# Isolated-Power-Section.net
KiCad netlist of a schematic drawn in Altium Designer
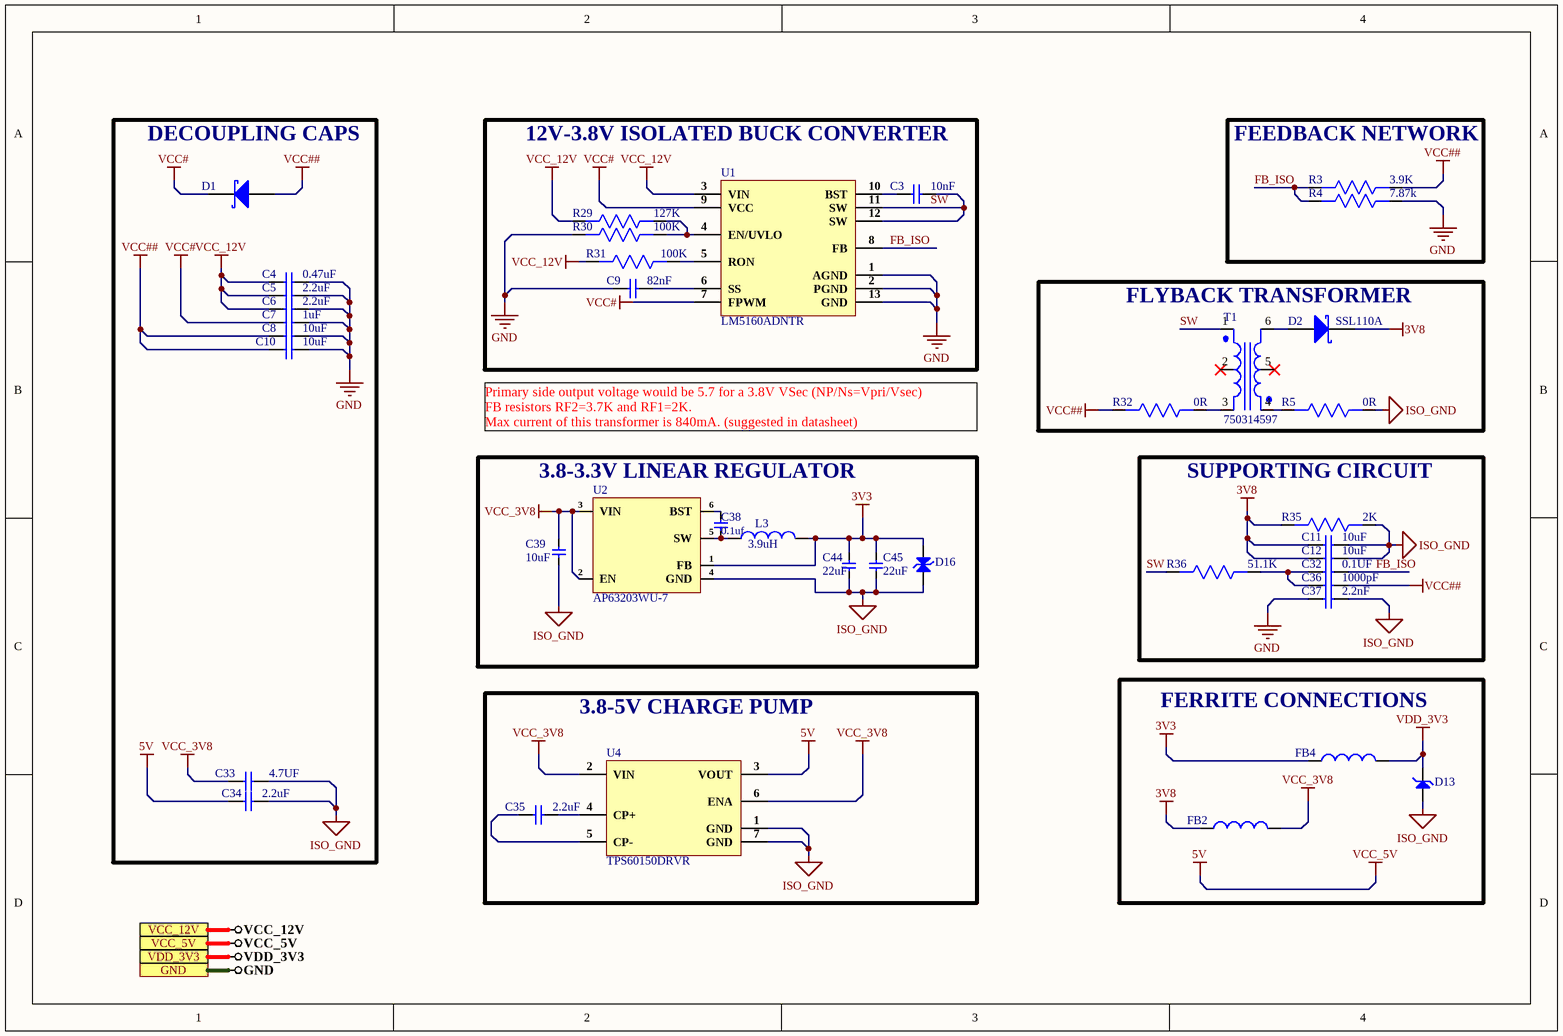
[diagram p0: Isolated-Power-Section.SchDoc]

(export (version "E")
  (design (tool "Eeschema 10.0.6"))
  (components
    (comp (ref "C3")
      (value "10nF")
      (footprint "Cap 0402")
      (description "CAP CER 10000PF 25V X7R 0402")
      (fields
        (field (name "MANUFACTURER") "Yageo")
        (field (name "MANUFACTURER PART NUMBER") "CC0402KRX7R8BB103")
      )
      (libsource (lib "Cole_Benson") (part "CC0402KRX7R8BB103"))
    )
    (comp (ref "C4")
      (value "0.47uF")
      (footprint "Cap 0402")
      (description "CAP CER 0.47UF 50V X5R 0402")
      (fields
        (field (name "MANUFACTURER") "Taiyo Yuden")
        (field (name "MANUFACTURER PART NUMBER") "UMK105ABJ474KV-F")
      )
      (libsource (lib "Cole_Benson") (part "UMK105ABJ474KV-F"))
    )
    (comp (ref "C5")
      (value "2.2uF")
      (footprint "Cap 0603")
      (description "CAP, 2.2µF, 35V, 10%, X5R, 0603")
      (fields
        (field (name "MANUFACTURER") "Murata")
        (field (name "MANUFACTURER PART NUMBER") "GRM188R6YA225KA12D")
      )
      (libsource (lib "Cole_Benson") (part "GRM188R6YA225KA12D"))
    )
    (comp (ref "C6")
      (value "2.2uF")
      (footprint "Cap 0603")
      (description "CAP, 2.2µF, 35V, 10%, X5R, 0603")
      (fields
        (field (name "MANUFACTURER") "Murata")
        (field (name "MANUFACTURER PART NUMBER") "GRM188R6YA225KA12D")
      )
      (libsource (lib "Cole_Benson") (part "GRM188R6YA225KA12D"))
    )
    (comp (ref "C7")
      (value "1uF")
      (footprint "Cap 0603")
      (description "CAP CER 1UF 25V X5R 0603")
      (fields
        (field (name "MANUFACTURER") "Yageo")
        (field (name "MANUFACTURER PART NUMBER") "CC0603KRX5R8BB105")
      )
      (libsource (lib "Cole_Benson") (part "CC0603KRX5R8BB105"))
    )
    (comp (ref "C8")
      (value "10uF")
      (footprint "Cap 0603")
      (description "10uF 35V X5R 20% Pad SMD 0603")
      (fields
        (field (name "MANUFACTURER") "Murata")
        (field (name "MANUFACTURER PART NUMBER") "GRM188R6YA106MA73D")
      )
      (libsource (lib "Cole_Benson") (part "GRM188R6YA106MA73D"))
    )
    (comp (ref "C9")
      (value "82nF")
      (footprint "Cap 0603")
      (description "CAP CER 0.082UF 50V X7R 0603")
      (fields
        (field (name "MANUFACTURER") "Yageo")
        (field (name "MANUFACTURER PART NUMBER") "CC0603KRX7R9BB823")
      )
      (libsource (lib "Cole_Benson") (part "CC0603KRX7R9BB823"))
    )
    (comp (ref "C10")
      (value "10uF")
      (footprint "Cap 0603")
      (description "10uF 35V X5R 20% Pad SMD 0603")
      (fields
        (field (name "MANUFACTURER") "Murata")
        (field (name "MANUFACTURER PART NUMBER") "GRM188R6YA106MA73D")
      )
      (libsource (lib "Cole_Benson") (part "GRM188R6YA106MA73D"))
    )
    (comp (ref "C11")
      (value "10uF")
      (footprint "Cap 0603")
      (description "10uF 35V X5R 20% Pad SMD 0603")
      (fields
        (field (name "MANUFACTURER") "Murata")
        (field (name "MANUFACTURER PART NUMBER") "GRM188R6YA106MA73D")
      )
      (libsource (lib "Cole_Benson") (part "GRM188R6YA106MA73D"))
    )
    (comp (ref "C12")
      (value "10uF")
      (footprint "Cap 0603")
      (description "10uF 35V X5R 20% Pad SMD 0603")
      (fields
        (field (name "MANUFACTURER") "Murata")
        (field (name "MANUFACTURER PART NUMBER") "GRM188R6YA106MA73D")
      )
      (libsource (lib "Cole_Benson") (part "GRM188R6YA106MA73D"))
    )
    (comp (ref "C32")
      (value "0.1UF")
      (footprint "Cap 0402")
      (description "CAP CER 0.1UF 50V X7R 0402")
      (fields
        (field (name "MANUFACTURER") "Samsung")
        (field (name "MANUFACTURER PART NUMBER") "CL05B104KB54PNC")
      )
      (libsource (lib "Cole_Benson") (part "CL05B104KB54PNC"))
    )
    (comp (ref "C33")
      (value "4.7UF")
      (footprint "Cap 0603")
      (description "CAP CER 4.7UF 25V X5R 0603")
      (fields
        (field (name "MANUFACTURER") "Samsung")
        (field (name "MANUFACTURER PART NUMBER") "CL10A475KA8NQNC")
      )
      (libsource (lib "Cole_Benson") (part "CL10A475KA8NQNC"))
    )
    (comp (ref "C34")
      (value "2.2uF")
      (footprint "Cap 0603")
      (description "CAP, 2.2µF, 35V, 10%, X5R, 0603")
      (fields
        (field (name "MANUFACTURER") "Murata")
        (field (name "MANUFACTURER PART NUMBER") "GRM188R6YA225KA12D")
      )
      (libsource (lib "Cole_Benson") (part "GRM188R6YA225KA12D"))
    )
    (comp (ref "C35")
      (value "2.2uF")
      (footprint "Cap 0603")
      (description "CAP, 2.2µF, 35V, 10%, X5R, 0603")
      (fields
        (field (name "MANUFACTURER") "Murata")
        (field (name "MANUFACTURER PART NUMBER") "GRM188R6YA225KA12D")
      )
      (libsource (lib "Cole_Benson") (part "GRM188R6YA225KA12D"))
    )
    (comp (ref "C36")
      (value "1000pF")
      (footprint "Cap 0402")
      (description "CAP CER 1000PF 100V X7R 0402")
      (fields
        (field (name "MANUFACTURER") "Wurth Electronics")
        (field (name "MANUFACTURER PART NUMBER") "885012205080")
      )
      (libsource (lib "Cole_Benson") (part "885012205080"))
    )
    (comp (ref "C37")
      (value "2.2nF")
      (footprint "Cap 0603")
      (description "CAP CER 2200PF 50V X7R 0603")
      (fields
        (field (name "MANUFACTURER") "Yageo")
        (field (name "MANUFACTURER PART NUMBER") "CC0603KRX7R9BB222")
      )
      (libsource (lib "Cole_Benson") (part "CC0603KRX7R9BB222"))
    )
    (comp (ref "C38")
      (value "0.1uf")
      (footprint "Cap-0402")
      (description "CAP CER 0.1UF 100V X5R 0402")
      (fields
        (field (name "MANUFACTURER") "Murata")
        (field (name "MANUFACTURER PART NUMBER") "GRM155R62A104KE14D")
      )
      (libsource (lib "eSpark Libraries") (part "GRM155R62A104KE14D"))
    )
    (comp (ref "C39")
      (value "10uF")
      (footprint "Cap-0603")
      (description "CAP CER 10UF 25V X5R 0603")
      (fields
        (field (name "MANUFACTURER") "TDK")
        (field (name "MANUFACTURER PART NUMBER") "C1608X5R1E106M080AC")
      )
      (libsource (lib "eSpark Libraries") (part "C1608X5R1E106M080AC"))
    )
    (comp (ref "C44")
      (value "22uF")
      (footprint "Cap-0805")
      (description "CAP CER 22UF 35V X5R 0805")
      (fields
        (field (name "MANUFACTURER") "TDK Corporation")
        (field (name "MANUFACTURER PART NUMBER") "C2012X5R1V226MT000E")
      )
      (libsource (lib "eSpark Libraries") (part "C2012X5R1V226MT000E"))
    )
    (comp (ref "C45")
      (value "22uF")
      (footprint "Cap-0805")
      (description "CAP CER 22UF 35V X5R 0805")
      (fields
        (field (name "MANUFACTURER") "TDK Corporation")
        (field (name "MANUFACTURER PART NUMBER") "C2012X5R1V226MT000E")
      )
      (libsource (lib "eSpark Libraries") (part "C2012X5R1V226MT000E"))
    )
    (comp (ref "D1")
      (value "CUS10S30,H3F")
      (footprint "CUS10S30,H3F")
      (description "Diode Schottky 30V 1A Surface Mount USC")
      (fields (field (name "MANUFACTURER") "Toshiba"))
      (libsource (lib "Cole_Benson") (part "CUS10S30,H3F"))
    )
    (comp (ref "D2")
      (value "SSL110A")
      (footprint "SMA")
      (description "500μA@100V 100V Single 600mV@1A 1A SMA Schottky Barrier Diodes (SBD) ROHS")
      (fields (field (name "MANUFACTURER") "Yangzhou"))
      (libsource (lib "Cole_Benson") (part "SSL110A"))
    )
    (comp (ref "D13")
      (value "1SMA5913BT3G-MS")
      (footprint "SMA")
      (description "Single 1.5W 3.13V~3.47V 3.3V SMA Zener Diodes ROHS")
      (fields (field (name "MANUFACTURER") "MSKSEMI") (field (name "LCSC PART NUMBER") "C18547722"))
      (libsource (lib "Cole_Benson") (part "1SMA5913BT3G-MS"))
    )
    (comp (ref "D16")
      (value "ESDM2033MX4T5G")
      (footprint "2-DFN (0.6x0.3)")
      (description "DIODE BIDIR ESD X4DFN2")
      (fields (field (name "MANUFACTURER") "ON Semiconductor") (field (name "LCSC PART NUMBER") "C896720"))
      (libsource (lib "Cole_Benson") (part "ESDM2033MX4T5G"))
    )
    (comp (ref "FB2")
      (value "MPZ1608S121ATDH5")
      (footprint "MPZ1608S121ATDH5")
      (description "Ferrite Beads Multi-Layer 120Ohm 25% 100MHz 2A 45mOhm DCR 0603 Automotive T/R")
      (fields (field (name "MANUFACTURER") "TDK") (field (name "TOLERANCE") "25%"))
      (libsource (lib "Cole_Benson") (part "MPZ1608S121ATDH5"))
    )
    (comp (ref "FB4")
      (value "MPZ1608S121ATDH5")
      (footprint "MPZ1608S121ATDH5")
      (description "Ferrite Beads Multi-Layer 120Ohm 25% 100MHz 2A 45mOhm DCR 0603 Automotive T/R")
      (fields (field (name "MANUFACTURER") "TDK") (field (name "TOLERANCE") "25%"))
      (libsource (lib "Cole_Benson") (part "MPZ1608S121ATDH5"))
    )
    (comp (ref "L3")
      (value "3.9uH")
      (footprint "FNR3015S3R9MT")
      (description "1.5A 3.9uH ±20% 1.4A SMD,3x3mm Power Inductors ROHS")
      (fields
        (field (name "MANUFACTURER") "cjiang")
        (field (name "MANUFACTURER PART NUMBER") "FNR3015S3R9MT")
      )
      (libsource (lib "Cole_Benson") (part "FNR3015S3R9MT"))
    )
    (comp (ref "R3")
      (value "3.9K")
      (footprint "Res0603")
      (description "Res 0603 3.9K Ohm 1% 0.1W(1/10W) ±100ppm/°C Pad SMD T/R")
      (fields
        (field (name "MANUFACTURER") "Yageo")
        (field (name "MANUFACTURER PART NUMBER") "RC0603FR-073K9L")
      )
      (libsource (lib "Cole_Benson") (part "RC0603FR-073K9L"))
    )
    (comp (ref "R4")
      (value "7.87k")
      (footprint "Res0603")
      (description "100mW 50V ±1% ±100ppm/℃ -55℃~+155℃ 7.87kΩ 0603 Chip Resistor - Surface Mount ROHS")
      (fields (field (name "MANUFACTURER") "FH") (field (name "MANUFACTURER PART NUMBER") "RS-03K7871FT"))
      (libsource (lib "Cole_Benson") (part "RS-03K7871FT"))
    )
    (comp (ref "R5")
      (value "0R")
      (footprint "Res0603")
      (description "RES SMD 0R, 1%, 0.1W, 0603")
      (fields
        (field (name "MANUFACTURER") "Yageo")
        (field (name "MANUFACTURER PART NUMBER") "RC0603FR-070RL")
      )
      (libsource (lib "Cole_Benson") (part "RC0603FR-070RL"))
    )
    (comp (ref "R29")
      (value "127K")
      (footprint "Res0603")
      (description "RES SMD 127K OHM 1% 1/10W 0603")
      (fields
        (field (name "MANUFACTURER") "Yageo")
        (field (name "MANUFACTURER PART NUMBER") "RT0603FRE07127KL")
      )
      (libsource (lib "Cole_Benson") (part "RT0603FRE07127KL"))
    )
    (comp (ref "R30")
      (value "100K")
      (footprint "Res0603")
      (description "Res Thick Film 0603 100K Ohm 5% 1/10W 100ppm/C Molded SMD SMD Paper T/R")
      (fields
        (field (name "MANUFACTURER") "Yageo")
        (field (name "MANUFACTURER PART NUMBER") "RC0603JR-07100KL")
      )
      (libsource (lib "Cole_Benson") (part "RC0603JR-07100KL"))
    )
    (comp (ref "R31")
      (value "100K")
      (footprint "Res0603")
      (description "Res Thick Film 0603 100K Ohm 5% 1/10W 100ppm/C Molded SMD SMD Paper T/R")
      (fields
        (field (name "MANUFACTURER") "Yageo")
        (field (name "MANUFACTURER PART NUMBER") "RC0603JR-07100KL")
      )
      (libsource (lib "Cole_Benson") (part "RC0603JR-07100KL"))
    )
    (comp (ref "R32")
      (value "0R")
      (footprint "Res0603")
      (description "RES SMD 0R, 1%, 0.1W, 0603")
      (fields
        (field (name "MANUFACTURER") "Yageo")
        (field (name "MANUFACTURER PART NUMBER") "RC0603FR-070RL")
      )
      (libsource (lib "Cole_Benson") (part "RC0603FR-070RL"))
    )
    (comp (ref "R35")
      (value "2K")
      (footprint "Res0603")
      (description "RES SMD 2K OHM 1% 1/10W 0603")
      (fields
        (field (name "MANUFACTURER") "Yageo")
        (field (name "MANUFACTURER PART NUMBER") "RC0603FR-072KL")
      )
      (libsource (lib "Cole_Benson") (part "RC0603FR-072KL"))
    )
    (comp (ref "R36")
      (value "51.1K")
      (footprint "Res0603")
      (description "Res SMD 0603 51.1K Ohm 0.1% 1/10W")
      (fields
        (field (name "MANUFACTURER") "Panasonic")
        (field (name "MANUFACTURER PART NUMBER") "ERA-3AEB5112V")
      )
      (libsource (lib "Cole_Benson") (part "ERA3AEB5112V"))
    )
    (comp (ref "T1")
      (value "750314597")
      (footprint "750314597")
      (description "XFRMR ISOL BUCK DC/DC CONV SMD")
      (fields (field (name "MANUFACTURER") "Wurth Electronics Midcom"))
      (libsource (lib "Cole_Benson") (part "750314597"))
    )
    (comp (ref "U1")
      (value "LM5160ADNTR")
      (footprint "LM5160ADNTR")
      (description "IC REG BUCK FLYBCK ADJ 12WSON")
      (fields (field (name "MANUFACTURER") "Texas Instruments"))
      (libsource (lib "Cole_Benson") (part "LM5160ADNTR"))
    )
    (comp (ref "U2")
      (value "AP63203WU-7")
      (footprint "TSOT-23-6")
      (description "IC REG BUCK 3.3V 2A TSOT26")
      (fields (field (name "MANUFACTURER") "Diodes") (field (name "LCSC PART NUMBER") "C780769"))
      (libsource (lib "eSpark Libraries") (part "AP63203WU-7"))
    )
    (comp (ref "U4")
      (value "TPS60150DRVR")
      (footprint "TPS60150DRVR")
      (description "IC REG CHARGE PUMP 5V 140MA 6SON")
      (fields (field (name "MANUFACTURER") "Texas Instruments"))
      (libsource (lib "Cole_Benson") (part "TPS60150DRVR"))
    )
  )
  (nets
    (net (code "1") (name "/FB_ISO") (class "Default")
      (node (ref "C32") (pin "2") (pinfunction "2_2") (pintype "passive"))
      (node (ref "R3") (pin "2") (pintype "passive"))
      (node (ref "R4") (pin "2") (pintype "passive"))
      (node (ref "U1") (pin "8") (pinfunction "FB_8") (pintype "passive"))
    )
    (net (code "2") (name "/SW") (class "Default")
      (node (ref "C3") (pin "2") (pinfunction "2_2") (pintype "passive"))
      (node (ref "R36") (pin "2") (pintype "passive"))
      (node (ref "T1") (pin "1") (pinfunction "PRI_1_1") (pintype "passive"))
      (node (ref "U1") (pin "11") (pinfunction "SW_11") (pintype "passive"))
      (node (ref "U1") (pin "12") (pinfunction "SW_12") (pintype "passive"))
    )
    (net (code "3") (name "3V3") (class "Default")
      (node (ref "C44") (pin "2") (pinfunction "2_2") (pintype "passive"))
      (node (ref "C45") (pin "2") (pinfunction "2_2") (pintype "passive"))
      (node (ref "D16") (pin "2") (pinfunction "A_2") (pintype "passive"))
      (node (ref "FB4") (pin "1") (pinfunction "1_1") (pintype "passive"))
      (node (ref "L3") (pin "2") (pinfunction "2_2") (pintype "passive"))
      (node (ref "U2") (pin "1") (pinfunction "FB_1") (pintype "passive"))
    )
    (net (code "4") (name "3V8") (class "Default")
      (node (ref "C11") (pin "1") (pinfunction "1_1") (pintype "passive"))
      (node (ref "C12") (pin "1") (pinfunction "1_1") (pintype "passive"))
      (node (ref "D2") (pin "1") (pinfunction "K_1") (pintype "passive"))
      (node (ref "FB2") (pin "1") (pinfunction "1_1") (pintype "passive"))
      (node (ref "R35") (pin "2") (pintype "passive"))
    )
    (net (code "5") (name "5V") (class "Default")
      (node (ref "C34") (pin "1") (pinfunction "1_1") (pintype "passive"))
      (node (ref "U4") (pin "3") (pinfunction "VOUT_3") (pintype "passive"))
    )
    (net (code "6") (name "GND") (class "Default")
      (node (ref "C10") (pin "2") (pinfunction "2_2") (pintype "passive"))
      (node (ref "C37") (pin "1") (pinfunction "1_1") (pintype "passive"))
      (node (ref "C4") (pin "2") (pinfunction "2_2") (pintype "passive"))
      (node (ref "C5") (pin "2") (pinfunction "2_2") (pintype "passive"))
      (node (ref "C6") (pin "2") (pinfunction "2_2") (pintype "passive"))
      (node (ref "C7") (pin "2") (pinfunction "2_2") (pintype "passive"))
      (node (ref "C8") (pin "2") (pinfunction "2_2") (pintype "passive"))
      (node (ref "C9") (pin "1") (pinfunction "1_1") (pintype "passive"))
      (node (ref "R30") (pin "2") (pintype "passive"))
      (node (ref "R4") (pin "1") (pintype "passive"))
      (node (ref "U1") (pin "1") (pinfunction "AGND_1") (pintype "passive"))
      (node (ref "U1") (pin "13") (pinfunction "GND_13") (pintype "passive"))
      (node (ref "U1") (pin "2") (pinfunction "PGND_2") (pintype "passive"))
    )
    (net (code "7") (name "ISO_GND") (class "Default")
      (node (ref "C11") (pin "2") (pinfunction "2_2") (pintype "passive"))
      (node (ref "C12") (pin "2") (pinfunction "2_2") (pintype "passive"))
      (node (ref "C33") (pin "2") (pinfunction "2_2") (pintype "passive"))
      (node (ref "C34") (pin "2") (pinfunction "2_2") (pintype "passive"))
      (node (ref "C37") (pin "2") (pinfunction "2_2") (pintype "passive"))
      (node (ref "C39") (pin "1") (pinfunction "1_1") (pintype "passive"))
      (node (ref "C44") (pin "1") (pinfunction "1_1") (pintype "passive"))
      (node (ref "C45") (pin "1") (pinfunction "1_1") (pintype "passive"))
      (node (ref "D13") (pin "2") (pinfunction "A_2") (pintype "passive"))
      (node (ref "D16") (pin "1") (pinfunction "A_1") (pintype "passive"))
      (node (ref "R35") (pin "1") (pintype "passive"))
      (node (ref "R5") (pin "1") (pintype "passive"))
      (node (ref "U2") (pin "4") (pinfunction "GND_4") (pintype "passive"))
      (node (ref "U4") (pin "1") (pinfunction "GND_1") (pintype "passive"))
      (node (ref "U4") (pin "7") (pinfunction "GND_7") (pintype "passive"))
    )
    (net (code "8") (name "Net-(C32-Pad1)") (class "Default")
      (node (ref "C32") (pin "1") (pinfunction "1_1") (pintype "passive"))
      (node (ref "C36") (pin "1") (pinfunction "1_1") (pintype "passive"))
      (node (ref "R36") (pin "1") (pintype "passive"))
    )
    (net (code "9") (name "Net-(D2-A)") (class "Default")
      (node (ref "D2") (pin "2") (pinfunction "A_2") (pintype "passive"))
      (node (ref "T1") (pin "6") (pinfunction "SEC_2_6") (pintype "passive"))
    )
    (net (code "10") (name "Net-(T1-PRI_2)") (class "Default")
      (node (ref "R32") (pin "1") (pintype "passive"))
      (node (ref "T1") (pin "3") (pinfunction "PRI_2_3") (pintype "passive"))
    )
    (net (code "11") (name "Net-(T1-SEC_1)") (class "Default")
      (node (ref "R5") (pin "2") (pintype "passive"))
      (node (ref "T1") (pin "4") (pinfunction "SEC_1_4") (pintype "passive"))
    )
    (net (code "12") (name "Net-(U1-BST)") (class "Default")
      (node (ref "C3") (pin "1") (pinfunction "1_1") (pintype "passive"))
      (node (ref "U1") (pin "10") (pinfunction "BST_10") (pintype "passive"))
    )
    (net (code "13") (name "Net-(U1-EN{slash}UVLO)") (class "Default")
      (node (ref "R29") (pin "1") (pintype "passive"))
      (node (ref "R30") (pin "1") (pintype "passive"))
      (node (ref "U1") (pin "4") (pinfunction "EN/UVLO_4") (pintype "passive"))
    )
    (net (code "14") (name "Net-(U1-RON)") (class "Default")
      (node (ref "R31") (pin "1") (pintype "passive"))
      (node (ref "U1") (pin "5") (pinfunction "RON_5") (pintype "passive"))
    )
    (net (code "15") (name "Net-(U1-SS)") (class "Default")
      (node (ref "C9") (pin "2") (pinfunction "2_2") (pintype "passive"))
      (node (ref "U1") (pin "6") (pinfunction "SS_6") (pintype "passive"))
    )
    (net (code "16") (name "Net-(U2-BST)") (class "Default")
      (node (ref "C38") (pin "2") (pinfunction "2_2") (pintype "passive"))
      (node (ref "U2") (pin "6") (pinfunction "BST_6") (pintype "passive"))
    )
    (net (code "17") (name "Net-(U2-SW)") (class "Default")
      (node (ref "C38") (pin "1") (pinfunction "1_1") (pintype "passive"))
      (node (ref "L3") (pin "1") (pinfunction "1_1") (pintype "passive"))
      (node (ref "U2") (pin "5") (pinfunction "SW_5") (pintype "passive"))
    )
    (net (code "18") (name "Net-(U4-CP+)") (class "Default")
      (node (ref "C35") (pin "2") (pinfunction "2_2") (pintype "passive"))
      (node (ref "U4") (pin "4") (pinfunction "CP+_4") (pintype "passive"))
    )
    (net (code "19") (name "Net-(U4-CP-)") (class "Default")
      (node (ref "C35") (pin "1") (pinfunction "1_1") (pintype "passive"))
      (node (ref "U4") (pin "5") (pinfunction "CP-_5") (pintype "passive"))
    )
    (net (code "20") (name "VCC#") (class "Default")
      (node (ref "C7") (pin "1") (pinfunction "1_1") (pintype "passive"))
      (node (ref "D1") (pin "1") (pinfunction "K_1") (pintype "passive"))
      (node (ref "U1") (pin "7") (pinfunction "FPWM_7") (pintype "passive"))
      (node (ref "U1") (pin "9") (pinfunction "VCC_9") (pintype "passive"))
    )
    (net (code "21") (name "VCC##") (class "Default")
      (node (ref "C10") (pin "1") (pinfunction "1_1") (pintype "passive"))
      (node (ref "C36") (pin "2") (pinfunction "2_2") (pintype "passive"))
      (node (ref "C8") (pin "1") (pinfunction "1_1") (pintype "passive"))
      (node (ref "D1") (pin "2") (pinfunction "A_2") (pintype "passive"))
      (node (ref "R3") (pin "1") (pintype "passive"))
      (node (ref "R32") (pin "2") (pintype "passive"))
    )
    (net (code "22") (name "VCC_3V8") (class "Default")
      (node (ref "C33") (pin "1") (pinfunction "1_1") (pintype "passive"))
      (node (ref "C39") (pin "2") (pinfunction "2_2") (pintype "passive"))
      (node (ref "FB2") (pin "2") (pinfunction "2_2") (pintype "passive"))
      (node (ref "U2") (pin "2") (pinfunction "EN_2") (pintype "passive"))
      (node (ref "U2") (pin "3") (pinfunction "VIN_3") (pintype "passive"))
      (node (ref "U4") (pin "2") (pinfunction "VIN_2") (pintype "passive"))
      (node (ref "U4") (pin "6") (pinfunction "ENA_6") (pintype "passive"))
    )
    (net (code "23") (name "VCC_12V") (class "Default")
      (node (ref "C4") (pin "1") (pinfunction "1_1") (pintype "passive"))
      (node (ref "C5") (pin "1") (pinfunction "1_1") (pintype "passive"))
      (node (ref "C6") (pin "1") (pinfunction "1_1") (pintype "passive"))
      (node (ref "R29") (pin "2") (pintype "passive"))
      (node (ref "R31") (pin "2") (pintype "passive"))
      (node (ref "U1") (pin "3") (pinfunction "VIN_3") (pintype "passive"))
    )
    (net (code "24") (name "VDD_3V3") (class "Default")
      (node (ref "D13") (pin "1") (pinfunction "C_1") (pintype "passive"))
      (node (ref "FB4") (pin "2") (pinfunction "2_2") (pintype "passive"))
    )
    (net (code "25") (name "unconnected-(T1-NC-Pad2)") (class "Default")
      (node (ref "T1") (pin "2") (pinfunction "NC_2") (pintype "passive+no_connect"))
    )
    (net (code "26") (name "unconnected-(T1-NC-Pad5)") (class "Default")
      (node (ref "T1") (pin "5") (pinfunction "NC_5") (pintype "passive+no_connect"))
    )
  )
)
